# CarrierDACs.net
KiCad netlist of a schematic drawn in Altium Designer
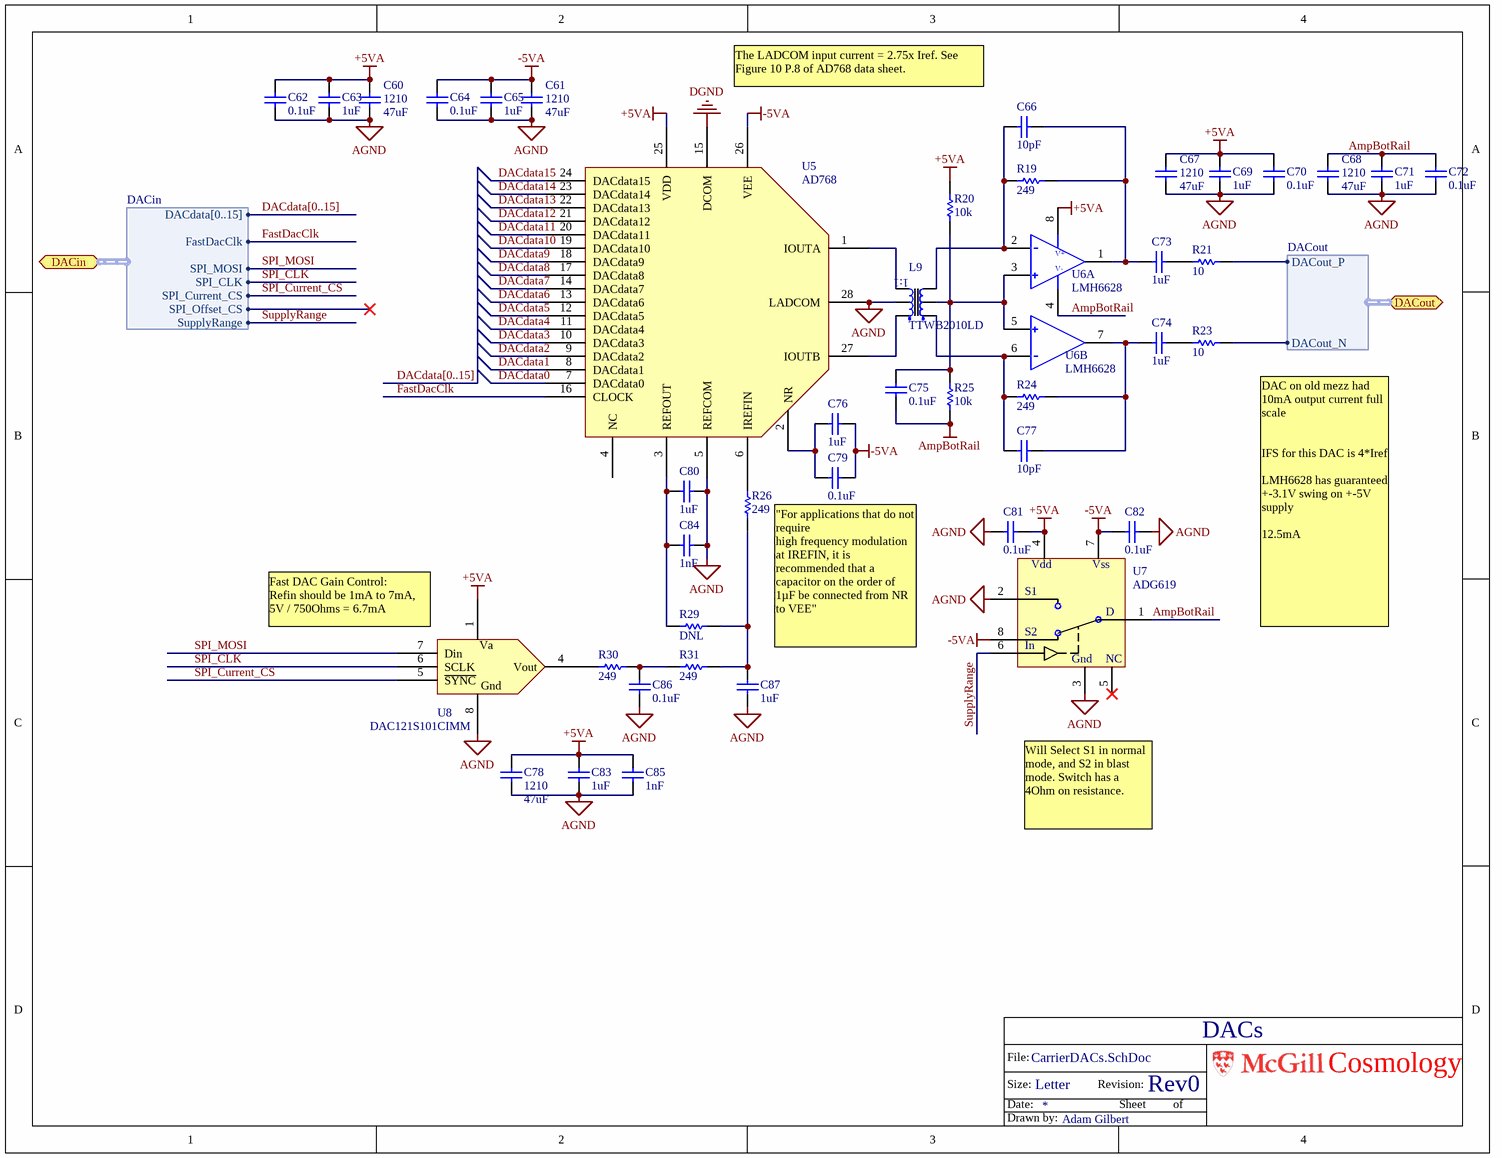
[diagram p0: CarrierDACs.SchDoc]

(export (version "E")
  (design (tool "Eeschema 10.0.6"))
  (components
    (comp (ref "C60")
      (value "47uF")
      (footprint "1210")
      (description "Capacitor, Ceramic, 1210")
      (fields
        (field (name "MANUFACTURER") "Taiyo Yuden")
        (field (name "MANUFACTURERS PART NUMBER") "LMK325B7476MM")
      )
      (libsource (lib "MGMEZZ04") (part "CAP 1210"))
    )
    (comp (ref "C61")
      (value "47uF")
      (footprint "1210")
      (description "Capacitor, Ceramic, 1210")
      (fields
        (field (name "MANUFACTURER") "Taiyo Yuden")
        (field (name "MANUFACTURERS PART NUMBER") "LMK325B7476MM")
      )
      (libsource (lib "MGMEZZ04") (part "CAP 1210"))
    )
    (comp (ref "C62")
      (value "0.1uF")
      (footprint "0603")
      (description "Capacitor, Ceramic, 0603")
      (fields (field (name "MANUFACTURER") "Generic"))
      (libsource (lib "MGMEZZ04") (part "CAP 0603"))
    )
    (comp (ref "C63")
      (value "1uF")
      (footprint "0603")
      (description "Capacitor, Ceramic, 0603")
      (fields (field (name "MANUFACTURER") "Generic"))
      (libsource (lib "MGMEZZ04") (part "CAP 0603"))
    )
    (comp (ref "C64")
      (value "0.1uF")
      (footprint "0603")
      (description "Capacitor, Ceramic, 0603")
      (fields (field (name "MANUFACTURER") "Generic"))
      (libsource (lib "MGMEZZ04") (part "CAP 0603"))
    )
    (comp (ref "C65")
      (value "1uF")
      (footprint "0603")
      (description "Capacitor, Ceramic, 0603")
      (fields (field (name "MANUFACTURER") "Generic"))
      (libsource (lib "MGMEZZ04") (part "CAP 0603"))
    )
    (comp (ref "C66")
      (value "10pF")
      (footprint "0603")
      (description "Capacitor, Ceramic, 0603")
      (fields (field (name "MANUFACTURER") "Generic"))
      (libsource (lib "MGMEZZ04") (part "CAP 0603"))
    )
    (comp (ref "C67")
      (value "47uF")
      (footprint "1210")
      (description "Capacitor, Ceramic, 1210")
      (fields
        (field (name "MANUFACTURER") "Taiyo Yuden")
        (field (name "MANUFACTURERS PART NUMBER") "LMK325B7476MM")
      )
      (libsource (lib "MGMEZZ04") (part "CAP 1210"))
    )
    (comp (ref "C68")
      (value "47uF")
      (footprint "1210")
      (description "Capacitor, Ceramic, 1210")
      (fields
        (field (name "MANUFACTURER") "Taiyo Yuden")
        (field (name "MANUFACTURERS PART NUMBER") "LMK325B7476MM")
      )
      (libsource (lib "MGMEZZ04") (part "CAP 1210"))
    )
    (comp (ref "C69")
      (value "1uF")
      (footprint "0603")
      (description "Capacitor, Ceramic, 0603")
      (fields (field (name "MANUFACTURER") "Generic"))
      (libsource (lib "MGMEZZ04") (part "CAP 0603"))
    )
    (comp (ref "C70")
      (value "0.1uF")
      (footprint "0603")
      (description "Capacitor, Ceramic, 0603")
      (fields (field (name "MANUFACTURER") "Generic"))
      (libsource (lib "MGMEZZ04") (part "CAP 0603"))
    )
    (comp (ref "C71")
      (value "1uF")
      (footprint "0603")
      (description "Capacitor, Ceramic, 0603")
      (fields (field (name "MANUFACTURER") "Generic"))
      (libsource (lib "MGMEZZ04") (part "CAP 0603"))
    )
    (comp (ref "C72")
      (value "0.1uF")
      (footprint "0603")
      (description "Capacitor, Ceramic, 0603")
      (fields (field (name "MANUFACTURER") "Generic"))
      (libsource (lib "MGMEZZ04") (part "CAP 0603"))
    )
    (comp (ref "C73")
      (value "1uF")
      (footprint "0603")
      (description "Capacitor, Ceramic, 0603")
      (fields (field (name "MANUFACTURER") "Generic"))
      (libsource (lib "MGMEZZ04") (part "CAP 0603"))
    )
    (comp (ref "C74")
      (value "1uF")
      (footprint "0603")
      (description "Capacitor, Ceramic, 0603")
      (fields (field (name "MANUFACTURER") "Generic"))
      (libsource (lib "MGMEZZ04") (part "CAP 0603"))
    )
    (comp (ref "C75")
      (value "0.1uF")
      (footprint "0603")
      (description "Capacitor, Ceramic, 0603")
      (fields (field (name "MANUFACTURER") "Generic"))
      (libsource (lib "MGMEZZ04") (part "CAP 0603"))
    )
    (comp (ref "C76")
      (value "1uF")
      (footprint "0603")
      (description "Capacitor, Ceramic, 0603")
      (fields (field (name "MANUFACTURER") "Generic"))
      (libsource (lib "MGMEZZ04") (part "CAP 0603"))
    )
    (comp (ref "C77")
      (value "10pF")
      (footprint "0603")
      (description "Capacitor, Ceramic, 0603")
      (fields (field (name "MANUFACTURER") "Generic"))
      (libsource (lib "MGMEZZ04") (part "CAP 0603"))
    )
    (comp (ref "C78")
      (value "47uF")
      (footprint "1210")
      (description "Capacitor, Ceramic, 1210")
      (fields
        (field (name "MANUFACTURER") "Taiyo Yuden")
        (field (name "MANUFACTURERS PART NUMBER") "LMK325B7476MM")
      )
      (libsource (lib "MGMEZZ04") (part "CAP 1210"))
    )
    (comp (ref "C79")
      (value "0.1uF")
      (footprint "0603")
      (description "Capacitor, Ceramic, 0603")
      (fields (field (name "MANUFACTURER") "Generic"))
      (libsource (lib "MGMEZZ04") (part "CAP 0603"))
    )
    (comp (ref "C80")
      (value "1uF")
      (footprint "0603")
      (description "Capacitor, Ceramic, 0603")
      (fields (field (name "MANUFACTURER") "Generic"))
      (libsource (lib "MGMEZZ04") (part "CAP 0603"))
    )
    (comp (ref "C81")
      (value "0.1uF")
      (footprint "0603")
      (description "Capacitor, Ceramic, 0603")
      (fields (field (name "MANUFACTURER") "Generic"))
      (libsource (lib "MGMEZZ04") (part "CAP 0603"))
    )
    (comp (ref "C82")
      (value "0.1uF")
      (footprint "0603")
      (description "Capacitor, Ceramic, 0603")
      (fields (field (name "MANUFACTURER") "Generic"))
      (libsource (lib "MGMEZZ04") (part "CAP 0603"))
    )
    (comp (ref "C83")
      (value "1uF")
      (footprint "0603")
      (description "Capacitor, Ceramic, 0603")
      (fields (field (name "MANUFACTURER") "Generic"))
      (libsource (lib "MGMEZZ04") (part "CAP 0603"))
    )
    (comp (ref "C84")
      (value "1nF")
      (footprint "0603")
      (description "Capacitor, Ceramic, 0603")
      (fields (field (name "MANUFACTURER") "Generic"))
      (libsource (lib "MGMEZZ04") (part "CAP 0603"))
    )
    (comp (ref "C85")
      (value "1nF")
      (footprint "0603")
      (description "Capacitor, Ceramic, 0603")
      (fields (field (name "MANUFACTURER") "Generic"))
      (libsource (lib "MGMEZZ04") (part "CAP 0603"))
    )
    (comp (ref "C86")
      (value "0.1uF")
      (footprint "0603")
      (description "Capacitor, Ceramic, 0603")
      (fields (field (name "MANUFACTURER") "Generic"))
      (libsource (lib "MGMEZZ04") (part "CAP 0603"))
    )
    (comp (ref "C87")
      (value "1uF")
      (footprint "0603")
      (description "Capacitor, Ceramic, 0603")
      (fields (field (name "MANUFACTURER") "Generic"))
      (libsource (lib "MGMEZZ04") (part "CAP 0603"))
    )
    (comp (ref "L9")
      (value "TTWB2010LD")
      (footprint "TTWB")
      (description "Transformer")
      (fields (field (name "MANUFACTURER") "Coil Craft"))
      (libsource (lib "MGMEZZ04") (part "TTWB2010LD"))
    )
    (comp (ref "R19")
      (value "249")
      (footprint "0603")
      (description "Resistor")
      (fields (field (name "MANUFACTURER") "Generic"))
      (libsource (lib "MGMEZZ04") (part "RES 0603"))
    )
    (comp (ref "R20")
      (value "10k")
      (footprint "0603")
      (description "Resistor")
      (fields (field (name "MANUFACTURER") "Generic"))
      (libsource (lib "MGMEZZ04") (part "RES 0603"))
    )
    (comp (ref "R21")
      (value "10")
      (footprint "0603")
      (description "Resistor")
      (fields (field (name "MANUFACTURER") "Generic"))
      (libsource (lib "MGMEZZ04") (part "RES 0603"))
    )
    (comp (ref "R23")
      (value "10")
      (footprint "0603")
      (description "Resistor")
      (fields (field (name "MANUFACTURER") "Generic"))
      (libsource (lib "MGMEZZ04") (part "RES 0603"))
    )
    (comp (ref "R24")
      (value "249")
      (footprint "0603")
      (description "Resistor")
      (fields (field (name "MANUFACTURER") "Generic"))
      (libsource (lib "MGMEZZ04") (part "RES 0603"))
    )
    (comp (ref "R25")
      (value "10k")
      (footprint "0603")
      (description "Resistor")
      (fields (field (name "MANUFACTURER") "Generic"))
      (libsource (lib "MGMEZZ04") (part "RES 0603"))
    )
    (comp (ref "R26")
      (value "249")
      (footprint "0603")
      (description "Resistor")
      (fields (field (name "MANUFACTURER") "Generic"))
      (libsource (lib "MGMEZZ04") (part "RES 0603"))
    )
    (comp (ref "R29")
      (value "DNL")
      (footprint "0603")
      (description "Resistor")
      (fields (field (name "MANUFACTURER") "Generic"))
      (libsource (lib "MGMEZZ04") (part "RES 0603"))
    )
    (comp (ref "R30")
      (value "249")
      (footprint "0603")
      (description "Resistor")
      (fields (field (name "MANUFACTURER") "Generic"))
      (libsource (lib "MGMEZZ04") (part "RES 0603"))
    )
    (comp (ref "R31")
      (value "249")
      (footprint "0603")
      (description "Resistor")
      (fields (field (name "MANUFACTURER") "Generic"))
      (libsource (lib "MGMEZZ04") (part "RES 0603"))
    )
    (comp (ref "U5")
      (value "AD768")
      (footprint "SOIC 28 300mils")
      (description "DAC 16bit 30MSPS")
      (fields
        (field (name "MANUFACTURERS PART NUMBER") "AD768ARZ")
        (field (name "MANUFACTURER") "Analog Devices")
      )
      (libsource (lib "MGMEZZ04") (part "AD768"))
    )
    (comp (ref "U6")
      (value "LMH6628")
      (footprint "SO8")
      (description "Dual Opamp 200Mhz GBP Soic 8")
      (fields
        (field (name "MANUFACTURERS PART NUMBER") "LMH6628MA/NOPB")
        (field (name "MANUFACTURER") "National Semiconductor")
      )
      (libsource (lib "MGMEZZ04") (part "LMH6628"))
    )
    (comp (ref "U7")
      (value "ADG619")
      (footprint "SOT23-8")
      (description "SPDT Switch +-5V 4 Ohm on resistance")
      (fields
        (field (name "MANUFACTURER") "Analog Devices")
        (field (name "MANUFACTURERS PART NUMBER") "ADG619BRTZ")
      )
      (libsource (lib "MGMEZZ04") (part "ADG619"))
    )
    (comp (ref "U8")
      (value "DAC121S101CIMM")
      (footprint "MSOP-8")
      (description "CONV D/A 12BIT MICROPWR 8MSOP")
      (fields
        (field (name "MANUFACTURER") "National Semiconductor")
        (field (name "MANUFACTURERS PART NUMBER") "DAC121S101CIMM/NOPB")
      )
      (libsource (lib "MGMEZZ04") (part "DAC121S101CIMM/NOPB"))
    )
  )
  (nets
    (net (code "3") (name "+5VA") (class "Default")
      (node (ref "C60") (pin "2") (pinfunction "2_2") (pintype "passive"))
      (node (ref "C62") (pin "2") (pinfunction "2_2") (pintype "passive"))
      (node (ref "C63") (pin "2") (pinfunction "2_2") (pintype "passive"))
      (node (ref "C67") (pin "2") (pinfunction "2_2") (pintype "passive"))
      (node (ref "C69") (pin "1") (pinfunction "1_1") (pintype "passive"))
      (node (ref "C70") (pin "1") (pinfunction "1_1") (pintype "passive"))
      (node (ref "C78") (pin "1") (pinfunction "1_1") (pintype "passive"))
      (node (ref "C81") (pin "1") (pinfunction "1_1") (pintype "passive"))
      (node (ref "C83") (pin "1") (pinfunction "1_1") (pintype "passive"))
      (node (ref "C85") (pin "1") (pinfunction "1_1") (pintype "passive"))
      (node (ref "R20") (pin "2") (pinfunction "2_2") (pintype "passive"))
      (node (ref "U5") (pin "25") (pinfunction "VDD_25") (pintype "passive"))
      (node (ref "U6") (pin "8") (pinfunction "V+_8") (pintype "power_in"))
      (node (ref "U7") (pin "4") (pinfunction "Vdd_4") (pintype "power_in"))
      (node (ref "U8") (pin "1") (pinfunction "Va_1") (pintype "passive"))
    )
    (net (code "4") (name "-5VA") (class "Default")
      (node (ref "C61") (pin "2") (pinfunction "2_2") (pintype "passive"))
      (node (ref "C64") (pin "2") (pinfunction "2_2") (pintype "passive"))
      (node (ref "C65") (pin "2") (pinfunction "2_2") (pintype "passive"))
      (node (ref "C76") (pin "1") (pinfunction "1_1") (pintype "passive"))
      (node (ref "C79") (pin "1") (pinfunction "1_1") (pintype "passive"))
      (node (ref "C82") (pin "2") (pinfunction "2_2") (pintype "passive"))
      (node (ref "U5") (pin "26") (pinfunction "VEE_26") (pintype "passive"))
      (node (ref "U7") (pin "7") (pinfunction "Vss_7") (pintype "power_in"))
      (node (ref "U7") (pin "8") (pinfunction "S2_8") (pintype "passive"))
    )
    (net (code "5") (name "/DACdata0") (class "Default")
      (node (ref "U5") (pin "7") (pinfunction "DACdata0_7") (pintype "passive"))
    )
    (net (code "6") (name "/DACdata1") (class "Default")
      (node (ref "U5") (pin "8") (pinfunction "DACdata1_8") (pintype "passive"))
    )
    (net (code "7") (name "/DACdata2") (class "Default")
      (node (ref "U5") (pin "9") (pinfunction "DACdata2_9") (pintype "passive"))
    )
    (net (code "8") (name "/DACdata3") (class "Default")
      (node (ref "U5") (pin "10") (pinfunction "DACdata3_10") (pintype "passive"))
    )
    (net (code "9") (name "/DACdata4") (class "Default")
      (node (ref "U5") (pin "11") (pinfunction "DACdata4_11") (pintype "passive"))
    )
    (net (code "10") (name "/DACdata5") (class "Default")
      (node (ref "U5") (pin "12") (pinfunction "DACdata5_12") (pintype "passive"))
    )
    (net (code "11") (name "/DACdata6") (class "Default")
      (node (ref "U5") (pin "13") (pinfunction "DACdata6_13") (pintype "passive"))
    )
    (net (code "12") (name "/DACdata7") (class "Default")
      (node (ref "U5") (pin "14") (pinfunction "DACdata7_14") (pintype "passive"))
    )
    (net (code "13") (name "/DACdata8") (class "Default")
      (node (ref "U5") (pin "17") (pinfunction "DACdata8_17") (pintype "passive"))
    )
    (net (code "14") (name "/DACdata9") (class "Default")
      (node (ref "U5") (pin "18") (pinfunction "DACdata9_18") (pintype "passive"))
    )
    (net (code "15") (name "/DACdata10") (class "Default")
      (node (ref "U5") (pin "19") (pinfunction "DACdata10_19") (pintype "passive"))
    )
    (net (code "16") (name "/DACdata11") (class "Default")
      (node (ref "U5") (pin "20") (pinfunction "DACdata11_20") (pintype "passive"))
    )
    (net (code "17") (name "/DACdata12") (class "Default")
      (node (ref "U5") (pin "21") (pinfunction "DACdata12_21") (pintype "passive"))
    )
    (net (code "18") (name "/DACdata13") (class "Default")
      (node (ref "U5") (pin "22") (pinfunction "DACdata13_22") (pintype "passive"))
    )
    (net (code "19") (name "/DACdata14") (class "Default")
      (node (ref "U5") (pin "23") (pinfunction "DACdata14_23") (pintype "passive"))
    )
    (net (code "20") (name "/DACdata15") (class "Default")
      (node (ref "U5") (pin "24") (pinfunction "DACdata15_24") (pintype "passive"))
    )
    (net (code "22") (name "/DACout_N") (class "Default")
      (node (ref "R23") (pin "2") (pinfunction "2_2") (pintype "passive"))
    )
    (net (code "23") (name "/DACout_P") (class "Default")
      (node (ref "R21") (pin "2") (pinfunction "2_2") (pintype "passive"))
    )
    (net (code "24") (name "/FastDacClk") (class "Default")
      (node (ref "U5") (pin "16") (pinfunction "CLOCK_16") (pintype "passive"))
    )
    (net (code "25") (name "/SPI_CLK") (class "Default")
      (node (ref "U8") (pin "6") (pinfunction "SCLK_6") (pintype "passive"))
    )
    (net (code "26") (name "/SPI_Current_CS") (class "Default")
      (node (ref "U8") (pin "5") (pinfunction "~{SYNC}_5") (pintype "passive"))
    )
    (net (code "27") (name "/SPI_MOSI") (class "Default")
      (node (ref "U8") (pin "7") (pinfunction "Din_7") (pintype "passive"))
    )
    (net (code "29") (name "/SupplyRange") (class "Default")
      (node (ref "U7") (pin "6") (pinfunction "In_6") (pintype "power_in"))
    )
    (net (code "32") (name "AGND") (class "Default")
      (node (ref "C60") (pin "1") (pinfunction "1_1") (pintype "passive"))
      (node (ref "C61") (pin "1") (pinfunction "1_1") (pintype "passive"))
      (node (ref "C62") (pin "1") (pinfunction "1_1") (pintype "passive"))
      (node (ref "C63") (pin "1") (pinfunction "1_1") (pintype "passive"))
      (node (ref "C64") (pin "1") (pinfunction "1_1") (pintype "passive"))
      (node (ref "C65") (pin "1") (pinfunction "1_1") (pintype "passive"))
      (node (ref "C67") (pin "1") (pinfunction "1_1") (pintype "passive"))
      (node (ref "C68") (pin "1") (pinfunction "1_1") (pintype "passive"))
      (node (ref "C69") (pin "2") (pinfunction "2_2") (pintype "passive"))
      (node (ref "C70") (pin "2") (pinfunction "2_2") (pintype "passive"))
      (node (ref "C71") (pin "2") (pinfunction "2_2") (pintype "passive"))
      (node (ref "C72") (pin "2") (pinfunction "2_2") (pintype "passive"))
      (node (ref "C78") (pin "2") (pinfunction "2_2") (pintype "passive"))
      (node (ref "C80") (pin "2") (pinfunction "2_2") (pintype "passive"))
      (node (ref "C81") (pin "2") (pinfunction "2_2") (pintype "passive"))
      (node (ref "C82") (pin "1") (pinfunction "1_1") (pintype "passive"))
      (node (ref "C83") (pin "2") (pinfunction "2_2") (pintype "passive"))
      (node (ref "C84") (pin "2") (pinfunction "2_2") (pintype "passive"))
      (node (ref "C85") (pin "2") (pinfunction "2_2") (pintype "passive"))
      (node (ref "C86") (pin "2") (pinfunction "2_2") (pintype "passive"))
      (node (ref "C87") (pin "2") (pinfunction "2_2") (pintype "passive"))
      (node (ref "L9") (pin "2") (pinfunction "PrimCent_2") (pintype "passive"))
      (node (ref "U5") (pin "28") (pinfunction "LADCOM_28") (pintype "passive"))
      (node (ref "U5") (pin "5") (pinfunction "REFCOM_5") (pintype "passive"))
      (node (ref "U7") (pin "2") (pinfunction "S1_2") (pintype "passive"))
      (node (ref "U7") (pin "3") (pinfunction "Gnd_3") (pintype "passive"))
      (node (ref "U8") (pin "8") (pinfunction "Gnd_8") (pintype "passive"))
    )
    (net (code "33") (name "AmpBotRail") (class "Default")
      (node (ref "C68") (pin "2") (pinfunction "2_2") (pintype "passive"))
      (node (ref "C71") (pin "1") (pinfunction "1_1") (pintype "passive"))
      (node (ref "C72") (pin "1") (pinfunction "1_1") (pintype "passive"))
      (node (ref "C75") (pin "2") (pinfunction "2_2") (pintype "passive"))
      (node (ref "R25") (pin "1") (pinfunction "1_1") (pintype "passive"))
      (node (ref "U6") (pin "4") (pinfunction "V-_4") (pintype "power_in"))
      (node (ref "U7") (pin "1") (pinfunction "D_1") (pintype "passive"))
    )
    (net (code "34") (name "DGND") (class "Default")
      (node (ref "U5") (pin "15") (pinfunction "DCOM_15") (pintype "passive"))
    )
    (net (code "35") (name "Net-(C73-Pad1)") (class "Default")
      (node (ref "C73") (pin "1") (pinfunction "1_1") (pintype "passive"))
      (node (ref "R21") (pin "1") (pinfunction "1_1") (pintype "passive"))
    )
    (net (code "36") (name "Net-(C74-Pad1)") (class "Default")
      (node (ref "C74") (pin "1") (pinfunction "1_1") (pintype "passive"))
      (node (ref "R23") (pin "1") (pinfunction "1_1") (pintype "passive"))
    )
    (net (code "37") (name "Net-(C86-Pad1)") (class "Default")
      (node (ref "C86") (pin "1") (pinfunction "1_1") (pintype "passive"))
      (node (ref "R30") (pin "1") (pinfunction "1_1") (pintype "passive"))
      (node (ref "R31") (pin "2") (pinfunction "2_2") (pintype "passive"))
    )
    (net (code "38") (name "Net-(C87-Pad1)") (class "Default")
      (node (ref "C87") (pin "1") (pinfunction "1_1") (pintype "passive"))
      (node (ref "R26") (pin "2") (pinfunction "2_2") (pintype "passive"))
      (node (ref "R29") (pin "2") (pinfunction "2_2") (pintype "passive"))
      (node (ref "R31") (pin "1") (pinfunction "1_1") (pintype "passive"))
    )
    (net (code "39") (name "Net-(L9-Prim)") (class "Default")
      (node (ref "L9") (pin "3") (pinfunction "Prim_3") (pintype "passive"))
      (node (ref "U5") (pin "1") (pinfunction "IOUTA_1") (pintype "passive"))
    )
    (net (code "40") (name "Net-(L9-PrimDot)") (class "Default")
      (node (ref "L9") (pin "1") (pinfunction "PrimDot_1") (pintype "passive"))
      (node (ref "U5") (pin "27") (pinfunction "IOUTB_27") (pintype "passive"))
    )
    (net (code "41") (name "Net-(L9-Sec)") (class "Default")
      (node (ref "C66") (pin "1") (pinfunction "1_1") (pintype "passive"))
      (node (ref "L9") (pin "4") (pinfunction "Sec_4") (pintype "passive"))
      (node (ref "R19") (pin "1") (pinfunction "1_1") (pintype "passive"))
      (node (ref "U6") (pin "2") (pinfunction "IN-_2") (pintype "passive"))
    )
    (net (code "42") (name "Net-(L9-SecCent)") (class "Default")
      (node (ref "C75") (pin "1") (pinfunction "1_1") (pintype "passive"))
      (node (ref "L9") (pin "5") (pinfunction "SecCent_5") (pintype "passive"))
      (node (ref "R20") (pin "1") (pinfunction "1_1") (pintype "passive"))
      (node (ref "R25") (pin "2") (pinfunction "2_2") (pintype "passive"))
      (node (ref "U6") (pin "3") (pinfunction "IN+_3") (pintype "passive"))
      (node (ref "U6") (pin "5") (pinfunction "IN+_5") (pintype "passive"))
    )
    (net (code "43") (name "Net-(L9-SecDot)") (class "Default")
      (node (ref "C77") (pin "1") (pinfunction "1_1") (pintype "passive"))
      (node (ref "L9") (pin "6") (pinfunction "SecDot_6") (pintype "passive"))
      (node (ref "R24") (pin "1") (pinfunction "1_1") (pintype "passive"))
      (node (ref "U6") (pin "6") (pinfunction "IN-_6") (pintype "passive"))
    )
    (net (code "44") (name "Net-(U5-IREFIN)") (class "Default")
      (node (ref "R26") (pin "1") (pinfunction "1_1") (pintype "passive"))
      (node (ref "U5") (pin "6") (pinfunction "IREFIN_6") (pintype "passive"))
    )
    (net (code "45") (name "Net-(U5-NR)") (class "Default")
      (node (ref "C76") (pin "2") (pinfunction "2_2") (pintype "passive"))
      (node (ref "C79") (pin "2") (pinfunction "2_2") (pintype "passive"))
      (node (ref "U5") (pin "2") (pinfunction "NR_2") (pintype "passive"))
    )
    (net (code "46") (name "Net-(U5-REFOUT)") (class "Default")
      (node (ref "C80") (pin "1") (pinfunction "1_1") (pintype "passive"))
      (node (ref "C84") (pin "1") (pinfunction "1_1") (pintype "passive"))
      (node (ref "R29") (pin "1") (pinfunction "1_1") (pintype "passive"))
      (node (ref "U5") (pin "3") (pinfunction "REFOUT_3") (pintype "passive"))
    )
    (net (code "47") (name "Net-(U6A-Out)") (class "Default")
      (node (ref "C66") (pin "2") (pinfunction "2_2") (pintype "passive"))
      (node (ref "C73") (pin "2") (pinfunction "2_2") (pintype "passive"))
      (node (ref "R19") (pin "2") (pinfunction "2_2") (pintype "passive"))
      (node (ref "U6") (pin "1") (pinfunction "Out_1") (pintype "passive"))
    )
    (net (code "48") (name "Net-(U6B-Out)") (class "Default")
      (node (ref "C74") (pin "2") (pinfunction "2_2") (pintype "passive"))
      (node (ref "C77") (pin "2") (pinfunction "2_2") (pintype "passive"))
      (node (ref "R24") (pin "2") (pinfunction "2_2") (pintype "passive"))
      (node (ref "U6") (pin "7") (pinfunction "Out_7") (pintype "passive"))
    )
    (net (code "49") (name "Net-(U8-Vout)") (class "Default")
      (node (ref "R30") (pin "2") (pinfunction "2_2") (pintype "passive"))
      (node (ref "U8") (pin "4") (pinfunction "Vout_4") (pintype "passive"))
    )
    (net (code "50") (name "unconnected-(U5-NC-Pad4)") (class "Default")
      (node (ref "U5") (pin "4") (pinfunction "NC_4") (pintype "passive"))
    )
    (net (code "51") (name "unconnected-(U7-NC-Pad5)") (class "Default")
      (node (ref "U7") (pin "5") (pinfunction "NC_5") (pintype "power_in+no_connect"))
    )
    (net (code "52") (name "unconnected-(U8-NC-Pad2)") (class "Default")
      (node (ref "U8") (pin "2") (pinfunction "NC_2") (pintype "passive"))
    )
    (net (code "53") (name "unconnected-(U8-NC-Pad3)") (class "Default")
      (node (ref "U8") (pin "3") (pinfunction "NC_3") (pintype "passive"))
    )
  )
)
